# lab_1_larionov_usb_rs232.net
KiCad netlist of a schematic drawn in Altium Designer
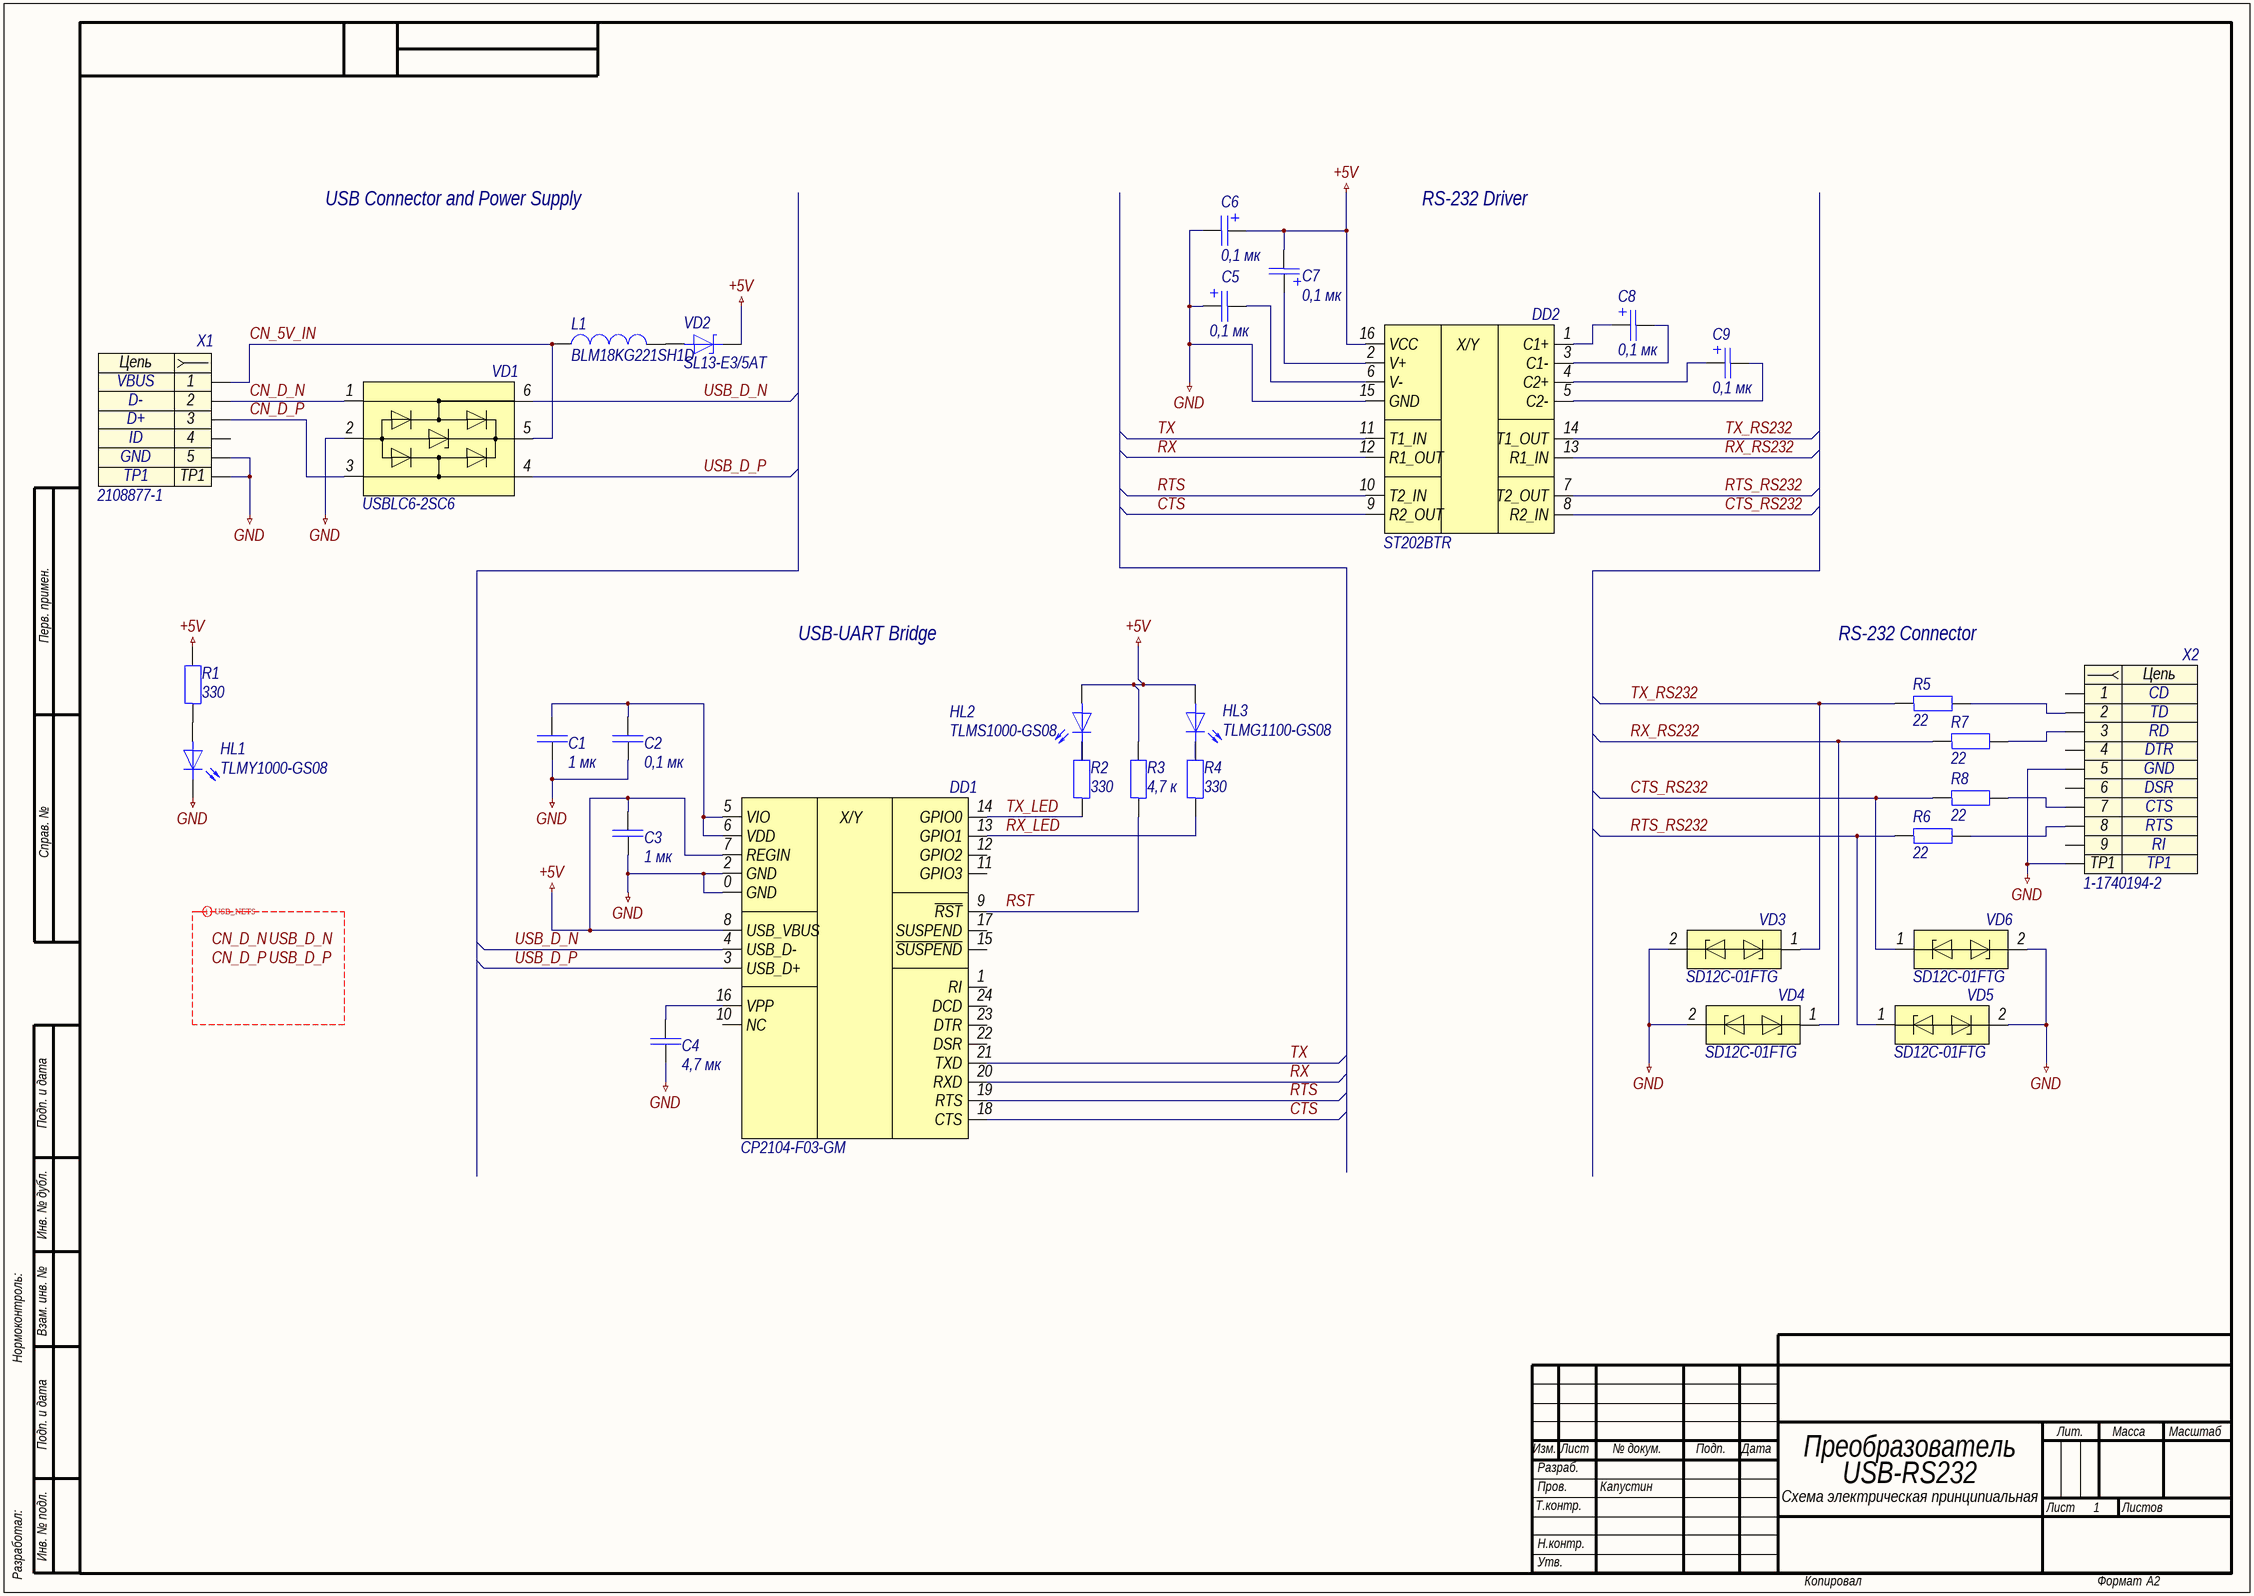
[diagram p0: lab_1_larionov_usb_rs232.SchDoc]

(export (version "E")
  (design (tool "Eeschema 10.0.6"))
  (components
    (comp (ref "C1")
      (value "1 мк")
      (footprint "C0603")
      (description "=Описание")
      (libsource (lib "Database_Students") (part "C-NONPOLAR"))
    )
    (comp (ref "C2")
      (value "0,1 мк")
      (footprint "C0603")
      (description "=Описание")
      (libsource (lib "Database_Students") (part "C-NONPOLAR"))
    )
    (comp (ref "C3")
      (value "1 мк")
      (footprint "C0603")
      (description "=Описание")
      (libsource (lib "Database_Students") (part "C-NONPOLAR"))
    )
    (comp (ref "C4")
      (value "4,7 мк")
      (footprint "C0603")
      (description "=Описание")
      (libsource (lib "Database_Students") (part "C-NONPOLAR"))
    )
    (comp (ref "C5")
      (value "0,1 мк")
      (footprint "C1206POLAR")
      (description "=Описание")
      (libsource (lib "Database_Students") (part "C-POLAR"))
    )
    (comp (ref "C6")
      (value "0,1 мк")
      (footprint "C1206POLAR")
      (description "=Описание")
      (libsource (lib "Database_Students") (part "C-POLAR"))
    )
    (comp (ref "C7")
      (value "0,1 мк")
      (footprint "C1206POLAR")
      (description "=Описание")
      (libsource (lib "Database_Students") (part "C-POLAR"))
    )
    (comp (ref "C8")
      (value "0,1 мк")
      (footprint "C1206POLAR")
      (description "=Описание")
      (libsource (lib "Database_Students") (part "C-POLAR"))
    )
    (comp (ref "C9")
      (value "0,1 мк")
      (footprint "C1206POLAR")
      (description "=Описание")
      (libsource (lib "Database_Students") (part "C-POLAR"))
    )
    (comp (ref "DD1")
      (value "CP2104-F03-GM")
      (footprint "QFN-24")
      (description "=Описание")
      (libsource (lib "Database_Students") (part "CP2104-F03-GM"))
    )
    (comp (ref "DD2")
      (value "ST202BTR")
      (footprint "TSSOP-16")
      (description "=Описание")
      (libsource (lib "Database_Students") (part "ST202B"))
    )
    (comp (ref "HL1")
      (value "TLMY1000-GS08")
      (footprint "HL0603")
      (description "=Описание")
      (libsource (lib "Database_Students") (part "HL-COMMON"))
    )
    (comp (ref "HL2")
      (value "TLMS1000-GS08")
      (footprint "HL0603")
      (description "=Описание")
      (libsource (lib "Database_Students") (part "HL-COMMON"))
    )
    (comp (ref "HL3")
      (value "TLMG1100-GS08")
      (footprint "HL0603")
      (description "=Описание")
      (libsource (lib "Database_Students") (part "HL-COMMON"))
    )
    (comp (ref "L1")
      (value "BLM18KG221SH1D")
      (footprint "FERRITE-BEAD")
      (description "=Описание")
      (libsource (lib "Database_Students") (part "FERRITE-BEAD"))
    )
    (comp (ref "R1")
      (value "330")
      (footprint "R0603")
      (description "=Описание")
      (libsource (lib "Database_Students") (part "R-COMMON"))
    )
    (comp (ref "R2")
      (value "330")
      (footprint "R0603")
      (description "=Описание")
      (libsource (lib "Database_Students") (part "R-COMMON"))
    )
    (comp (ref "R3")
      (value "4,7 к")
      (footprint "R0603")
      (description "=Описание")
      (libsource (lib "Database_Students") (part "R-COMMON"))
    )
    (comp (ref "R4")
      (value "330")
      (footprint "R0603")
      (description "=Описание")
      (libsource (lib "Database_Students") (part "R-COMMON"))
    )
    (comp (ref "R5")
      (value "22")
      (footprint "R0603")
      (description "=Описание")
      (libsource (lib "Database_Students") (part "R-COMMON"))
    )
    (comp (ref "R6")
      (value "22")
      (footprint "R0603")
      (description "=Описание")
      (libsource (lib "Database_Students") (part "R-COMMON"))
    )
    (comp (ref "R7")
      (value "22")
      (footprint "R0603")
      (description "=Описание")
      (libsource (lib "Database_Students") (part "R-COMMON"))
    )
    (comp (ref "R8")
      (value "22")
      (footprint "R0603")
      (description "=Описание")
      (libsource (lib "Database_Students") (part "R-COMMON"))
    )
    (comp (ref "VD1")
      (value "USBLC6-2SC6")
      (footprint "SOT23-6L")
      (description "=Описание")
      (libsource (lib "Database_Students") (part "USBLC6-2SC6"))
    )
    (comp (ref "VD2")
      (value "SL13-E3/5AT")
      (footprint "DO-214AC")
      (description "=Описание")
      (libsource (lib "Database_Students") (part "DIODE-SCHOTTKY"))
    )
    (comp (ref "VD3")
      (value "SD12C-01FTG")
      (footprint "SOD323")
      (description "=Описание")
      (libsource (lib "") (part "SD12C-01FTG_1"))
    )
    (comp (ref "VD4")
      (value "SD12C-01FTG")
      (footprint "SOD323")
      (description "=Описание")
      (libsource (lib "") (part "SD12C-01FTG_1"))
    )
    (comp (ref "VD5")
      (value "SD12C-01FTG")
      (footprint "SOD323")
      (description "=Описание")
      (libsource (lib "Database_Students") (part "SD12C-01FTG"))
    )
    (comp (ref "VD6")
      (value "SD12C-01FTG")
      (footprint "SOD323")
      (description "=Описание")
      (libsource (lib "Database_Students") (part "SD12C-01FTG"))
    )
    (comp (ref "X1")
      (value "2108877-1")
      (footprint "2108877-1")
      (libsource (lib "Database_Students") (part "HEADER-5-TP1-SCT"))
    )
    (comp (ref "X2")
      (value "1-1740194-2")
      (footprint "1-1740194-2")
      (libsource (lib "Database_Students") (part "HEADER-9-TP1-SCT"))
    )
  )
  (nets
    (net (code "1") (name "+5V") (class "Default")
      (node (ref "C3") (pin "2") (pinfunction "2_2") (pintype "passive"))
      (node (ref "C6") (pin "1") (pinfunction "1_1") (pintype "passive"))
      (node (ref "C7") (pin "2") (pinfunction "2_2") (pintype "passive"))
      (node (ref "DD1") (pin "7") (pinfunction "REGIN_7") (pintype "passive"))
      (node (ref "DD1") (pin "8") (pinfunction "USB_VBUS_8") (pintype "passive"))
      (node (ref "DD2") (pin "16") (pinfunction "VCC_16") (pintype "passive"))
      (node (ref "HL2") (pin "2") (pinfunction "2_2") (pintype "passive"))
      (node (ref "HL3") (pin "2") (pinfunction "2_2") (pintype "passive"))
      (node (ref "R1") (pin "2") (pinfunction "2_2") (pintype "passive"))
      (node (ref "R3") (pin "2") (pinfunction "2_2") (pintype "passive"))
      (node (ref "VD2") (pin "1") (pinfunction "1_1") (pintype "passive"))
    )
    (net (code "2") (name "/CN_5V_IN") (class "Default")
      (node (ref "L1") (pin "1") (pinfunction "1_1") (pintype "passive"))
      (node (ref "VD1") (pin "5") (pinfunction "5_5") (pintype "passive"))
      (node (ref "X1") (pin "1") (pinfunction "1_1") (pintype "passive"))
    )
    (net (code "3") (name "/CN_D_N") (class "Default")
      (node (ref "VD1") (pin "1") (pinfunction "1_1") (pintype "passive"))
      (node (ref "X1") (pin "2") (pinfunction "2_2") (pintype "passive"))
    )
    (net (code "4") (name "/CN_D_P") (class "Default")
      (node (ref "VD1") (pin "3") (pinfunction "3_3") (pintype "passive"))
      (node (ref "X1") (pin "3") (pinfunction "3_3") (pintype "passive"))
    )
    (net (code "5") (name "/CTS") (class "Default")
      (node (ref "DD1") (pin "18") (pinfunction "CTS_18") (pintype "passive"))
      (node (ref "DD2") (pin "9") (pinfunction "R2_OUT_9") (pintype "passive"))
    )
    (net (code "6") (name "/CTS_RS232") (class "Default")
      (node (ref "DD2") (pin "8") (pinfunction "R2_IN_8") (pintype "passive"))
      (node (ref "R8") (pin "1") (pinfunction "1_1") (pintype "passive"))
      (node (ref "VD6") (pin "1") (pinfunction "1_1") (pintype "passive"))
    )
    (net (code "7") (name "/RST") (class "Default")
      (node (ref "DD1") (pin "9") (pinfunction "~{RST}_9") (pintype "passive"))
      (node (ref "R3") (pin "1") (pinfunction "1_1") (pintype "passive"))
    )
    (net (code "8") (name "/RTS") (class "Default")
      (node (ref "DD1") (pin "19") (pinfunction "RTS_19") (pintype "passive"))
      (node (ref "DD2") (pin "10") (pinfunction "T2_IN_10") (pintype "passive"))
    )
    (net (code "9") (name "/RTS_RS232") (class "Default")
      (node (ref "DD2") (pin "7") (pinfunction "T2_OUT_7") (pintype "passive"))
      (node (ref "R6") (pin "1") (pinfunction "1_1") (pintype "passive"))
      (node (ref "VD5") (pin "1") (pinfunction "1_1") (pintype "passive"))
    )
    (net (code "10") (name "/RX") (class "Default")
      (node (ref "DD1") (pin "20") (pinfunction "RXD_20") (pintype "passive"))
      (node (ref "DD2") (pin "12") (pinfunction "R1_OUT_12") (pintype "passive"))
    )
    (net (code "11") (name "/RX_LED") (class "Default")
      (node (ref "DD1") (pin "13") (pinfunction "GPIO1_13") (pintype "passive"))
      (node (ref "R4") (pin "1") (pinfunction "1_1") (pintype "passive"))
    )
    (net (code "12") (name "/RX_RS232") (class "Default")
      (node (ref "DD2") (pin "13") (pinfunction "R1_IN_13") (pintype "passive"))
      (node (ref "R7") (pin "1") (pinfunction "1_1") (pintype "passive"))
      (node (ref "VD4") (pin "1") (pinfunction "1_1") (pintype "passive"))
    )
    (net (code "13") (name "/TX") (class "Default")
      (node (ref "DD1") (pin "21") (pinfunction "TXD_21") (pintype "passive"))
      (node (ref "DD2") (pin "11") (pinfunction "T1_IN_11") (pintype "passive"))
    )
    (net (code "14") (name "/TX_LED") (class "Default")
      (node (ref "DD1") (pin "14") (pinfunction "GPIO0_14") (pintype "passive"))
      (node (ref "R2") (pin "1") (pinfunction "1_1") (pintype "passive"))
    )
    (net (code "15") (name "/TX_RS232") (class "Default")
      (node (ref "DD2") (pin "14") (pinfunction "T1_OUT_14") (pintype "passive"))
      (node (ref "R5") (pin "1") (pinfunction "1_1") (pintype "passive"))
      (node (ref "VD3") (pin "1") (pinfunction "1_1") (pintype "passive"))
    )
    (net (code "16") (name "/USB_D_N") (class "Default")
      (node (ref "DD1") (pin "4") (pinfunction "USB_D-_4") (pintype "passive"))
      (node (ref "VD1") (pin "6") (pinfunction "6_6") (pintype "passive"))
    )
    (net (code "17") (name "/USB_D_P") (class "Default")
      (node (ref "DD1") (pin "3") (pinfunction "USB_D+_3") (pintype "passive"))
      (node (ref "VD1") (pin "4") (pinfunction "4_4") (pintype "passive"))
    )
    (net (code "18") (name "GND") (class "Default")
      (node (ref "C1") (pin "1") (pinfunction "1_1") (pintype "passive"))
      (node (ref "C2") (pin "1") (pinfunction "1_1") (pintype "passive"))
      (node (ref "C3") (pin "1") (pinfunction "1_1") (pintype "passive"))
      (node (ref "C4") (pin "1") (pinfunction "1_1") (pintype "passive"))
      (node (ref "C5") (pin "1") (pinfunction "1_1") (pintype "passive"))
      (node (ref "C6") (pin "2") (pinfunction "2_2") (pintype "passive"))
      (node (ref "DD1") (pin "0") (pinfunction "GND_0") (pintype "passive"))
      (node (ref "DD1") (pin "2") (pinfunction "GND_2") (pintype "passive"))
      (node (ref "DD2") (pin "15") (pinfunction "GND_15") (pintype "passive"))
      (node (ref "HL1") (pin "1") (pinfunction "1_1") (pintype "passive"))
      (node (ref "VD1") (pin "2") (pinfunction "2_2") (pintype "passive"))
      (node (ref "VD3") (pin "2") (pinfunction "2_2") (pintype "passive"))
      (node (ref "VD4") (pin "2") (pinfunction "2_2") (pintype "passive"))
      (node (ref "VD5") (pin "2") (pinfunction "2_2") (pintype "passive"))
      (node (ref "VD6") (pin "2") (pinfunction "2_2") (pintype "passive"))
      (node (ref "X1") (pin "5") (pinfunction "5_5") (pintype "passive"))
      (node (ref "X1") (pin "TP1") (pinfunction "TP1_TP1") (pintype "passive"))
      (node (ref "X2") (pin "5") (pinfunction "5_5") (pintype "passive"))
      (node (ref "X2") (pin "TP1") (pinfunction "TP1_TP1") (pintype "passive"))
    )
    (net (code "19") (name "Net-(DD1-VDD)") (class "Default")
      (node (ref "C1") (pin "2") (pinfunction "2_2") (pintype "passive"))
      (node (ref "C2") (pin "2") (pinfunction "2_2") (pintype "passive"))
      (node (ref "DD1") (pin "5") (pinfunction "VIO_5") (pintype "passive"))
      (node (ref "DD1") (pin "6") (pinfunction "VDD_6") (pintype "passive"))
    )
    (net (code "20") (name "Net-(DD1-VPP)") (class "Default")
      (node (ref "C4") (pin "2") (pinfunction "2_2") (pintype "passive"))
      (node (ref "DD1") (pin "16") (pinfunction "VPP_16") (pintype "passive"))
    )
    (net (code "21") (name "Net-(DD2-C1+)") (class "Default")
      (node (ref "C8") (pin "1") (pinfunction "1_1") (pintype "passive"))
      (node (ref "DD2") (pin "1") (pinfunction "C1+_1") (pintype "passive"))
    )
    (net (code "22") (name "Net-(DD2-C1-)") (class "Default")
      (node (ref "C8") (pin "2") (pinfunction "2_2") (pintype "passive"))
      (node (ref "DD2") (pin "3") (pinfunction "C1-_3") (pintype "passive"))
    )
    (net (code "23") (name "Net-(DD2-C2+)") (class "Default")
      (node (ref "C9") (pin "1") (pinfunction "1_1") (pintype "passive"))
      (node (ref "DD2") (pin "4") (pinfunction "C2+_4") (pintype "passive"))
    )
    (net (code "24") (name "Net-(DD2-C2-)") (class "Default")
      (node (ref "C9") (pin "2") (pinfunction "2_2") (pintype "passive"))
      (node (ref "DD2") (pin "5") (pinfunction "C2-_5") (pintype "passive"))
    )
    (net (code "25") (name "Net-(DD2-V+)") (class "Default")
      (node (ref "C7") (pin "1") (pinfunction "1_1") (pintype "passive"))
      (node (ref "DD2") (pin "2") (pinfunction "V+_2") (pintype "passive"))
    )
    (net (code "26") (name "Net-(DD2-V-)") (class "Default")
      (node (ref "C5") (pin "2") (pinfunction "2_2") (pintype "passive"))
      (node (ref "DD2") (pin "6") (pinfunction "V-_6") (pintype "passive"))
    )
    (net (code "27") (name "Net-(HL1-Pad2)") (class "Default")
      (node (ref "HL1") (pin "2") (pinfunction "2_2") (pintype "passive"))
      (node (ref "R1") (pin "1") (pinfunction "1_1") (pintype "passive"))
    )
    (net (code "28") (name "Net-(HL2-Pad1)") (class "Default")
      (node (ref "HL2") (pin "1") (pinfunction "1_1") (pintype "passive"))
      (node (ref "R2") (pin "2") (pinfunction "2_2") (pintype "passive"))
    )
    (net (code "29") (name "Net-(HL3-Pad1)") (class "Default")
      (node (ref "HL3") (pin "1") (pinfunction "1_1") (pintype "passive"))
      (node (ref "R4") (pin "2") (pinfunction "2_2") (pintype "passive"))
    )
    (net (code "30") (name "Net-(L1-Pad2)") (class "Default")
      (node (ref "L1") (pin "2") (pinfunction "2_2") (pintype "passive"))
      (node (ref "VD2") (pin "2") (pinfunction "2_2") (pintype "passive"))
    )
    (net (code "31") (name "Net-(R5-Pad2)") (class "Default")
      (node (ref "R5") (pin "2") (pinfunction "2_2") (pintype "passive"))
      (node (ref "X2") (pin "2") (pinfunction "2_2") (pintype "passive"))
    )
    (net (code "32") (name "Net-(R6-Pad2)") (class "Default")
      (node (ref "R6") (pin "2") (pinfunction "2_2") (pintype "passive"))
      (node (ref "X2") (pin "8") (pinfunction "8_8") (pintype "passive"))
    )
    (net (code "33") (name "Net-(R7-Pad2)") (class "Default")
      (node (ref "R7") (pin "2") (pinfunction "2_2") (pintype "passive"))
      (node (ref "X2") (pin "3") (pinfunction "3_3") (pintype "passive"))
    )
    (net (code "34") (name "Net-(R8-Pad2)") (class "Default")
      (node (ref "R8") (pin "2") (pinfunction "2_2") (pintype "passive"))
      (node (ref "X2") (pin "7") (pinfunction "7_7") (pintype "passive"))
    )
    (net (code "35") (name "unconnected-(DD1-DCD-Pad24)") (class "Default")
      (node (ref "DD1") (pin "24") (pinfunction "DCD_24") (pintype "passive"))
    )
    (net (code "36") (name "unconnected-(DD1-DSR-Pad22)") (class "Default")
      (node (ref "DD1") (pin "22") (pinfunction "DSR_22") (pintype "passive"))
    )
    (net (code "37") (name "unconnected-(DD1-DTR-Pad23)") (class "Default")
      (node (ref "DD1") (pin "23") (pinfunction "DTR_23") (pintype "passive"))
    )
    (net (code "38") (name "unconnected-(DD1-GPIO2-Pad12)") (class "Default")
      (node (ref "DD1") (pin "12") (pinfunction "GPIO2_12") (pintype "passive"))
    )
    (net (code "39") (name "unconnected-(DD1-GPIO3-Pad11)") (class "Default")
      (node (ref "DD1") (pin "11") (pinfunction "GPIO3_11") (pintype "passive"))
    )
    (net (code "40") (name "unconnected-(DD1-NC-Pad10)") (class "Default")
      (node (ref "DD1") (pin "10") (pinfunction "NC_10") (pintype "passive"))
    )
    (net (code "41") (name "unconnected-(DD1-RI-Pad1)") (class "Default")
      (node (ref "DD1") (pin "1") (pinfunction "RI_1") (pintype "passive"))
    )
    (net (code "42") (name "unconnected-(DD1-SUSPEND-Pad17)") (class "Default")
      (node (ref "DD1") (pin "17") (pinfunction "SUSPEND_17") (pintype "passive"))
    )
    (net (code "43") (name "unconnected-(DD1-~{SUSPEND}-Pad15)") (class "Default")
      (node (ref "DD1") (pin "15") (pinfunction "~{SUSPEND}_15") (pintype "passive"))
    )
    (net (code "44") (name "unconnected-(X1-Pad4)") (class "Default")
      (node (ref "X1") (pin "4") (pinfunction "4_4") (pintype "passive"))
    )
    (net (code "45") (name "unconnected-(X2-Pad1)") (class "Default")
      (node (ref "X2") (pin "1") (pinfunction "1_1") (pintype "passive"))
    )
    (net (code "46") (name "unconnected-(X2-Pad4)") (class "Default")
      (node (ref "X2") (pin "4") (pinfunction "4_4") (pintype "passive"))
    )
    (net (code "47") (name "unconnected-(X2-Pad6)") (class "Default")
      (node (ref "X2") (pin "6") (pinfunction "6_6") (pintype "passive"))
    )
    (net (code "48") (name "unconnected-(X2-Pad9)") (class "Default")
      (node (ref "X2") (pin "9") (pinfunction "9_9") (pintype "passive"))
    )
  )
)
